# plc_module_xs_00001_001_DALI_Master.net
KiCad netlist of a schematic drawn in Altium Designer
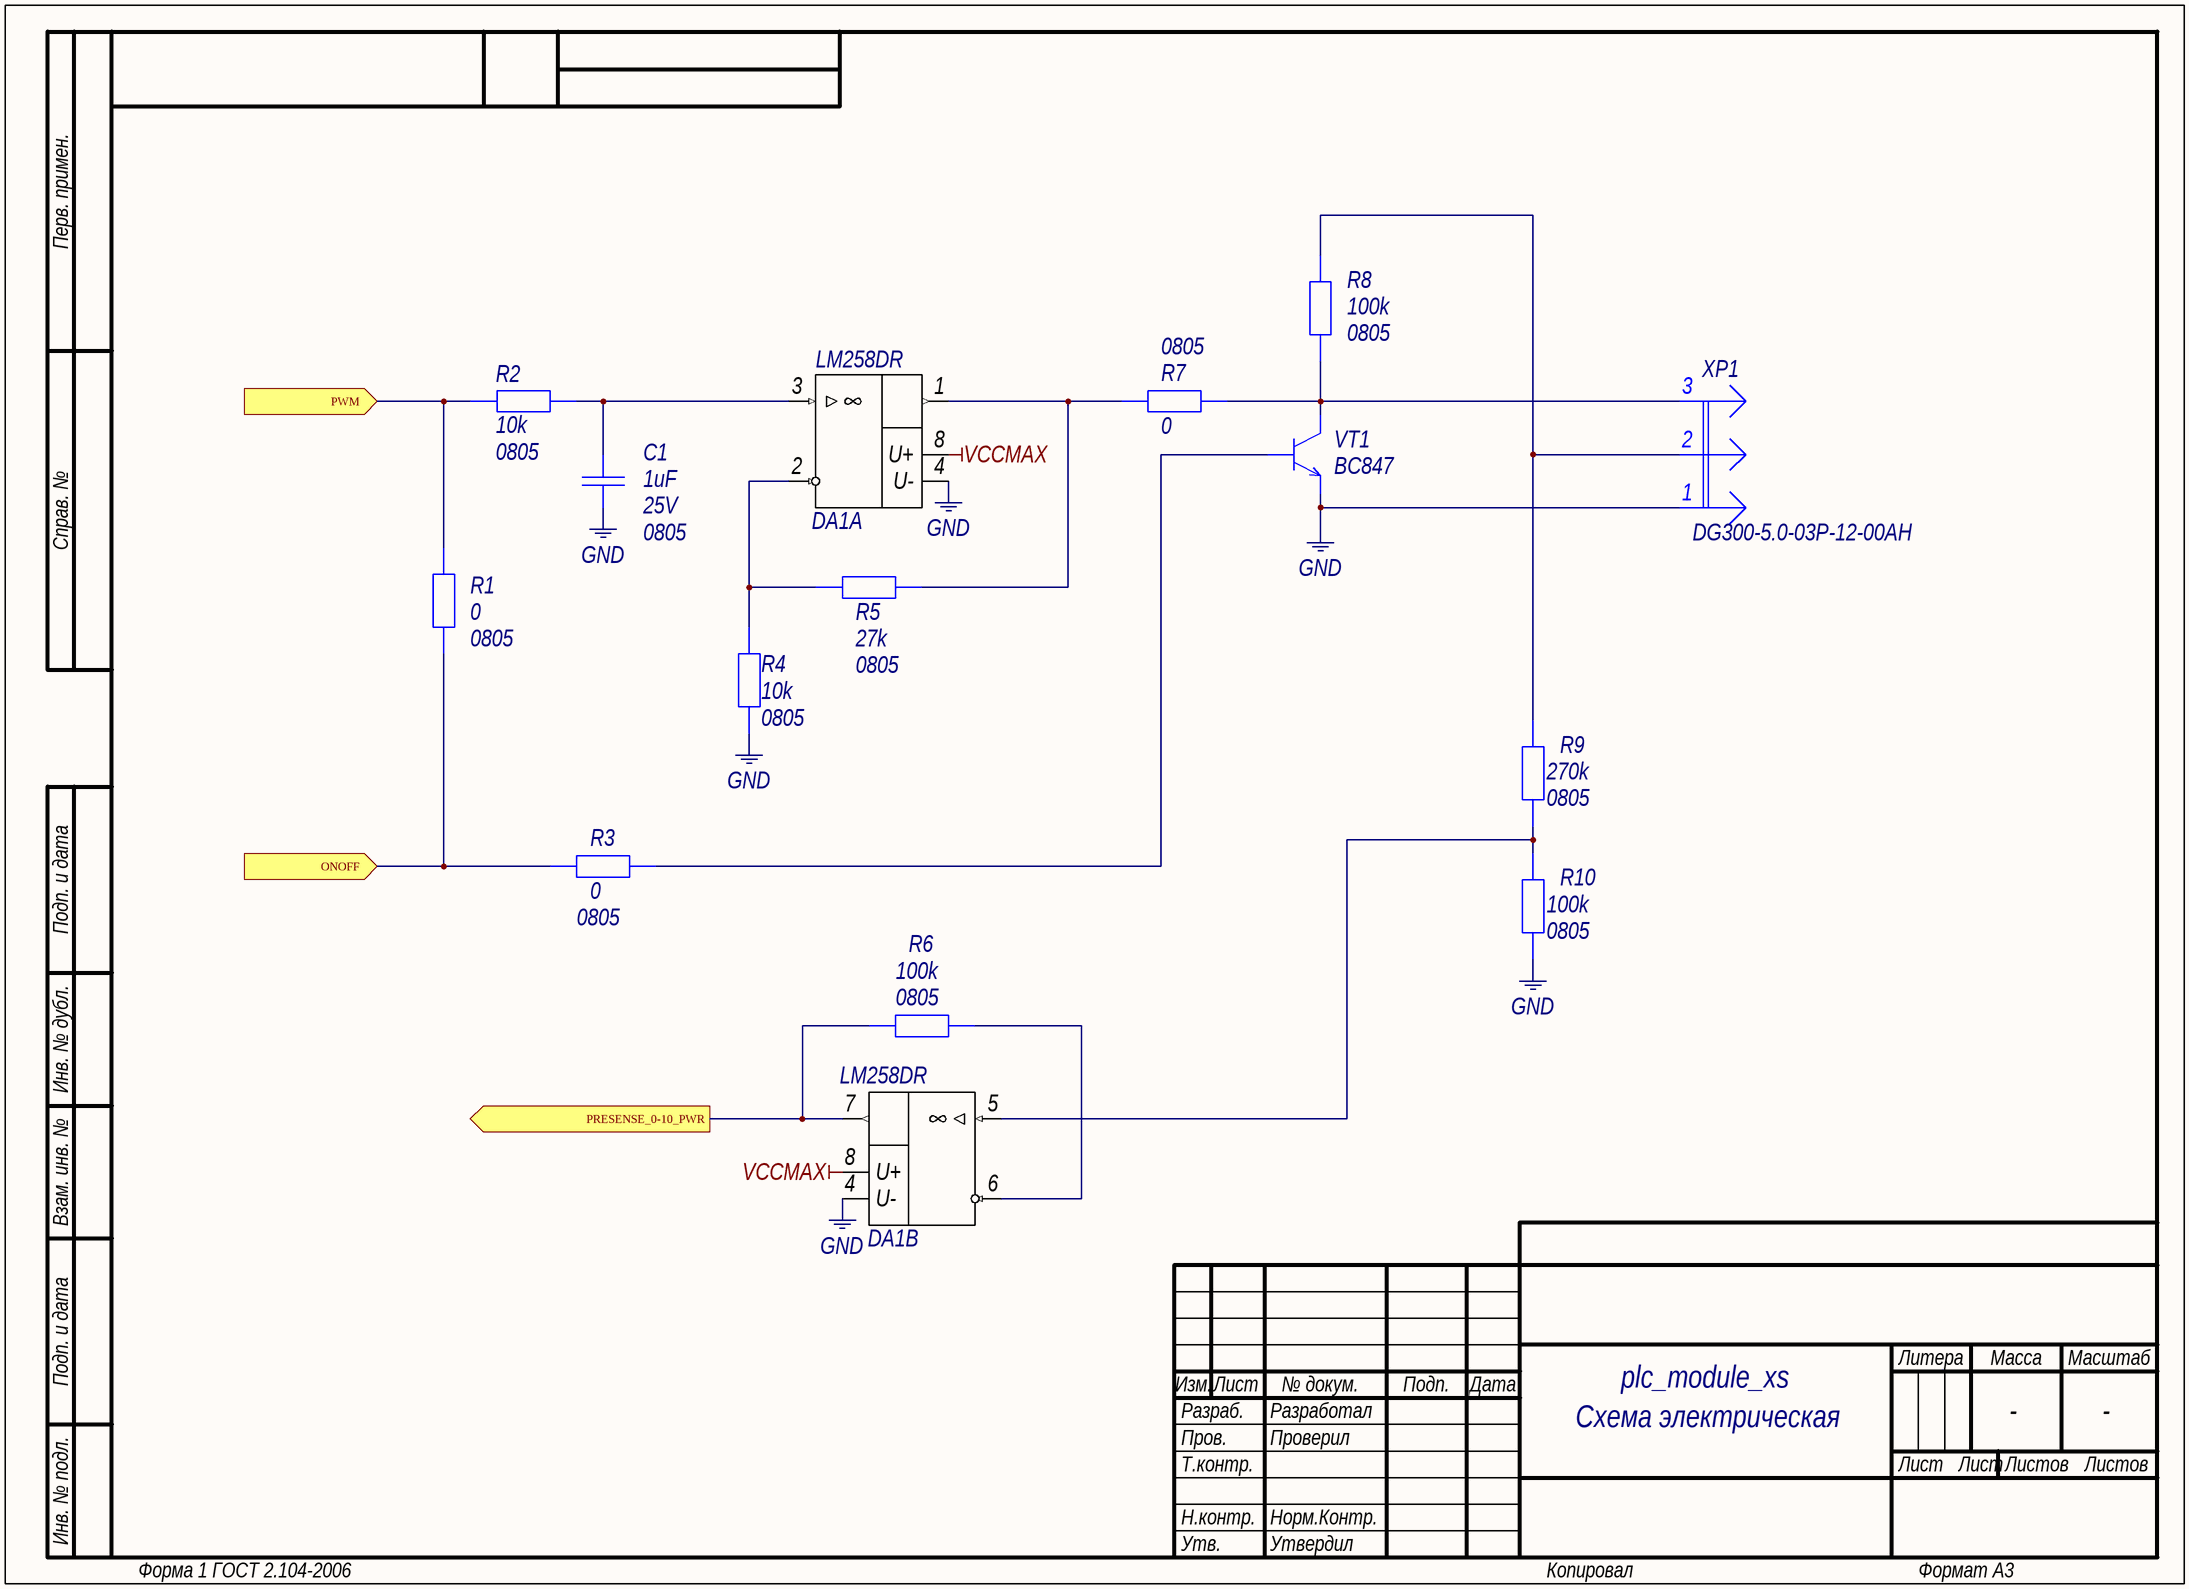
[diagram p0: plc_module_xs.00001.001_DALI_Master.SchDoc]

(export (version "E")
  (design (tool "Eeschema 10.0.6"))
  (components
    (comp (ref "C1")
      (value "1uF")
      (footprint "0805")
      (fields
        (field (name "PART NUMBER") "GRM219R71E105KA88D")
        (field (name "VOLTAGE") "25V")
        (field (name "TOLERANCE") "±10%")
        (field (name "MANUFACTURER") "Murata")
        (field (name "PUBLISHER") "Andrew Danich")
      )
      (libsource (lib "GOST_IMPORT_PARTS") (part "Capacitor"))
    )
    (comp (ref "DA1")
      (value "LM258DR")
      (footprint "SOIC-8")
      (fields (field (name "PUBLISHER") "Andrew Danich"))
      (libsource (lib "GOST_IMPORT_PARTS") (part "OPA-2-8p"))
    )
    (comp (ref "R1")
      (value "0")
      (footprint "0805")
      (fields
        (field (name "PART NUMBER") "RC0805JR-070RL")
        (field (name "TOLERANCE") "±5%")
        (field (name "MANUFACTURER") "Yageo")
        (field (name "PUBLISHER") "Andrew Danich")
      )
      (libsource (lib "GOST_IMPORT_PARTS") (part "Resistor"))
    )
    (comp (ref "R2")
      (value "10k")
      (footprint "0805")
      (fields
        (field (name "PART NUMBER") "RC0805JR-0710KL")
        (field (name "TOLERANCE") "±5%")
        (field (name "MANUFACTURER") "Yageo")
        (field (name "PUBLISHER") "Andrew Danich")
      )
      (libsource (lib "GOST_IMPORT_PARTS") (part "Resistor"))
    )
    (comp (ref "R3")
      (value "0")
      (footprint "0805")
      (fields
        (field (name "PART NUMBER") "RC0805JR-070RL")
        (field (name "TOLERANCE") "±5%")
        (field (name "MANUFACTURER") "Yageo")
        (field (name "PUBLISHER") "Andrew Danich")
      )
      (libsource (lib "GOST_IMPORT_PARTS") (part "Resistor"))
    )
    (comp (ref "R4")
      (value "10k")
      (footprint "0805")
      (fields
        (field (name "PART NUMBER") "RC0805JR-0710KL")
        (field (name "TOLERANCE") "±5%")
        (field (name "MANUFACTURER") "Yageo")
        (field (name "PUBLISHER") "Andrew Danich")
      )
      (libsource (lib "GOST_IMPORT_PARTS") (part "Resistor"))
    )
    (comp (ref "R5")
      (value "27k")
      (footprint "0805")
      (fields
        (field (name "PART NUMBER") "RC0805JR-0727KL")
        (field (name "TOLERANCE") "±5%")
        (field (name "MANUFACTURER") "Yageo")
        (field (name "PUBLISHER") "Andrew Danich")
      )
      (libsource (lib "GOST_IMPORT_PARTS") (part "Resistor"))
    )
    (comp (ref "R6")
      (value "100k")
      (footprint "0805")
      (fields
        (field (name "PART NUMBER") "RC0805JR-07100KL")
        (field (name "TOLERANCE") "±5%")
        (field (name "MANUFACTURER") "Yageo")
        (field (name "PUBLISHER") "Andrew Danich")
      )
      (libsource (lib "GOST_IMPORT_PARTS") (part "Resistor"))
    )
    (comp (ref "R7")
      (value "0")
      (footprint "0805")
      (fields
        (field (name "PART NUMBER") "RC0805JR-070RL")
        (field (name "TOLERANCE") "±5%")
        (field (name "MANUFACTURER") "Yageo")
        (field (name "PUBLISHER") "Andrew Danich")
      )
      (libsource (lib "GOST_IMPORT_PARTS") (part "Resistor"))
    )
    (comp (ref "R8")
      (value "100k")
      (footprint "0805")
      (fields
        (field (name "PART NUMBER") "RC0805JR-07100KL")
        (field (name "TOLERANCE") "±5%")
        (field (name "MANUFACTURER") "Yageo")
        (field (name "PUBLISHER") "Andrew Danich")
      )
      (libsource (lib "GOST_IMPORT_PARTS") (part "Resistor"))
    )
    (comp (ref "R9")
      (value "270k")
      (footprint "0805")
      (fields
        (field (name "PART NUMBER") "RC0805JR-07270KL")
        (field (name "TOLERANCE") "±5%")
        (field (name "MANUFACTURER") "Yageo")
        (field (name "PUBLISHER") "Andrew Danich")
      )
      (libsource (lib "GOST_IMPORT_PARTS") (part "Resistor"))
    )
    (comp (ref "R10")
      (value "100k")
      (footprint "0805")
      (fields
        (field (name "PART NUMBER") "RC0805JR-07100KL")
        (field (name "TOLERANCE") "±5%")
        (field (name "MANUFACTURER") "Yageo")
        (field (name "PUBLISHER") "Andrew Danich")
      )
      (libsource (lib "GOST_IMPORT_PARTS") (part "Resistor"))
    )
    (comp (ref "VT1")
      (value "BC847")
      (footprint "SOT-23")
      (fields (field (name "Comment") "BJT-NPN") (field (name "PUBLISHER") "Andrew Danich"))
      (libsource (lib "GOST_IMPORT_PARTS") (part "BJT-NPN"))
    )
    (comp (ref "XP1")
      (value "DG300-5.0-03P-12-00AH")
      (footprint "PHOENIX_1715734")
      (fields (field (name "Comment") "GND PWR CTRL") (field (name "PUBLISHER") "Andrew Danich"))
      (libsource (lib "GOST_IMPORT_PARTS") (part "Con-3-M"))
    )
  )
  (nets
    (net (code "1") (name "/ONOFF") (class "Default")
      (node (ref "R1") (pin "2") (pinfunction "2_2") (pintype "passive"))
      (node (ref "R3") (pin "1") (pinfunction "1_1") (pintype "passive"))
    )
    (net (code "2") (name "/PRESENSE_0-10_PWR") (class "Default")
      (node (ref "DA1") (pin "7") (pinfunction "OUT_7") (pintype "output"))
      (node (ref "R6") (pin "1") (pinfunction "1_1") (pintype "passive"))
    )
    (net (code "3") (name "/PWM") (class "Default")
      (node (ref "R1") (pin "1") (pinfunction "1_1") (pintype "passive"))
      (node (ref "R2") (pin "2") (pinfunction "2_2") (pintype "passive"))
    )
    (net (code "4") (name "GND") (class "Default")
      (node (ref "C1") (pin "1") (pinfunction "1_1") (pintype "passive"))
      (node (ref "DA1") (pin "4") (pinfunction "U-_4") (pintype "power_in"))
      (node (ref "R10") (pin "1") (pinfunction "1_1") (pintype "passive"))
      (node (ref "R4") (pin "2") (pinfunction "2_2") (pintype "passive"))
      (node (ref "VT1") (pin "3") (pinfunction "Э_3") (pintype "passive"))
      (node (ref "XP1") (pin "1") (pintype "passive"))
    )
    (net (code "5") (name "Net-(DA1A-IN+)") (class "Default")
      (node (ref "C1") (pin "2") (pinfunction "2_2") (pintype "passive"))
      (node (ref "DA1") (pin "3") (pinfunction "IN+_3") (pintype "input"))
      (node (ref "R2") (pin "1") (pinfunction "1_1") (pintype "passive"))
    )
    (net (code "6") (name "Net-(DA1A-IN-)") (class "Default")
      (node (ref "DA1") (pin "2") (pinfunction "IN-_2") (pintype "input"))
      (node (ref "R4") (pin "1") (pinfunction "1_1") (pintype "passive"))
      (node (ref "R5") (pin "1") (pinfunction "1_1") (pintype "passive"))
    )
    (net (code "7") (name "Net-(DA1A-OUT)") (class "Default")
      (node (ref "DA1") (pin "1") (pinfunction "OUT_1") (pintype "output"))
      (node (ref "R5") (pin "2") (pinfunction "2_2") (pintype "passive"))
      (node (ref "R7") (pin "1") (pinfunction "1_1") (pintype "passive"))
    )
    (net (code "8") (name "Net-(DA1B-IN+)") (class "Default")
      (node (ref "DA1") (pin "5") (pinfunction "IN+_5") (pintype "input"))
      (node (ref "R10") (pin "2") (pinfunction "2_2") (pintype "passive"))
      (node (ref "R9") (pin "1") (pinfunction "1_1") (pintype "passive"))
    )
    (net (code "9") (name "Net-(DA1B-IN-)") (class "Default")
      (node (ref "DA1") (pin "6") (pinfunction "IN-_6") (pintype "input"))
      (node (ref "R6") (pin "2") (pinfunction "2_2") (pintype "passive"))
    )
    (net (code "10") (name "Net-(R8-Pad2)") (class "Default")
      (node (ref "R8") (pin "2") (pinfunction "2_2") (pintype "passive"))
      (node (ref "R9") (pin "2") (pinfunction "2_2") (pintype "passive"))
      (node (ref "XP1") (pin "2") (pintype "passive"))
    )
    (net (code "11") (name "Net-(VT1-Б)") (class "Default")
      (node (ref "R3") (pin "2") (pinfunction "2_2") (pintype "passive"))
      (node (ref "VT1") (pin "1") (pinfunction "Б_1") (pintype "passive"))
    )
    (net (code "12") (name "Net-(VT1-К)") (class "Default")
      (node (ref "R7") (pin "2") (pinfunction "2_2") (pintype "passive"))
      (node (ref "R8") (pin "1") (pinfunction "1_1") (pintype "passive"))
      (node (ref "VT1") (pin "2") (pinfunction "К_2") (pintype "passive"))
      (node (ref "XP1") (pin "3") (pintype "passive"))
    )
    (net (code "13") (name "VCCMAX") (class "Default")
      (node (ref "DA1") (pin "8") (pinfunction "U+_8") (pintype "power_in"))
    )
  )
)
